# Rev01.net
KiCad netlist of a schematic drawn in EAGLE
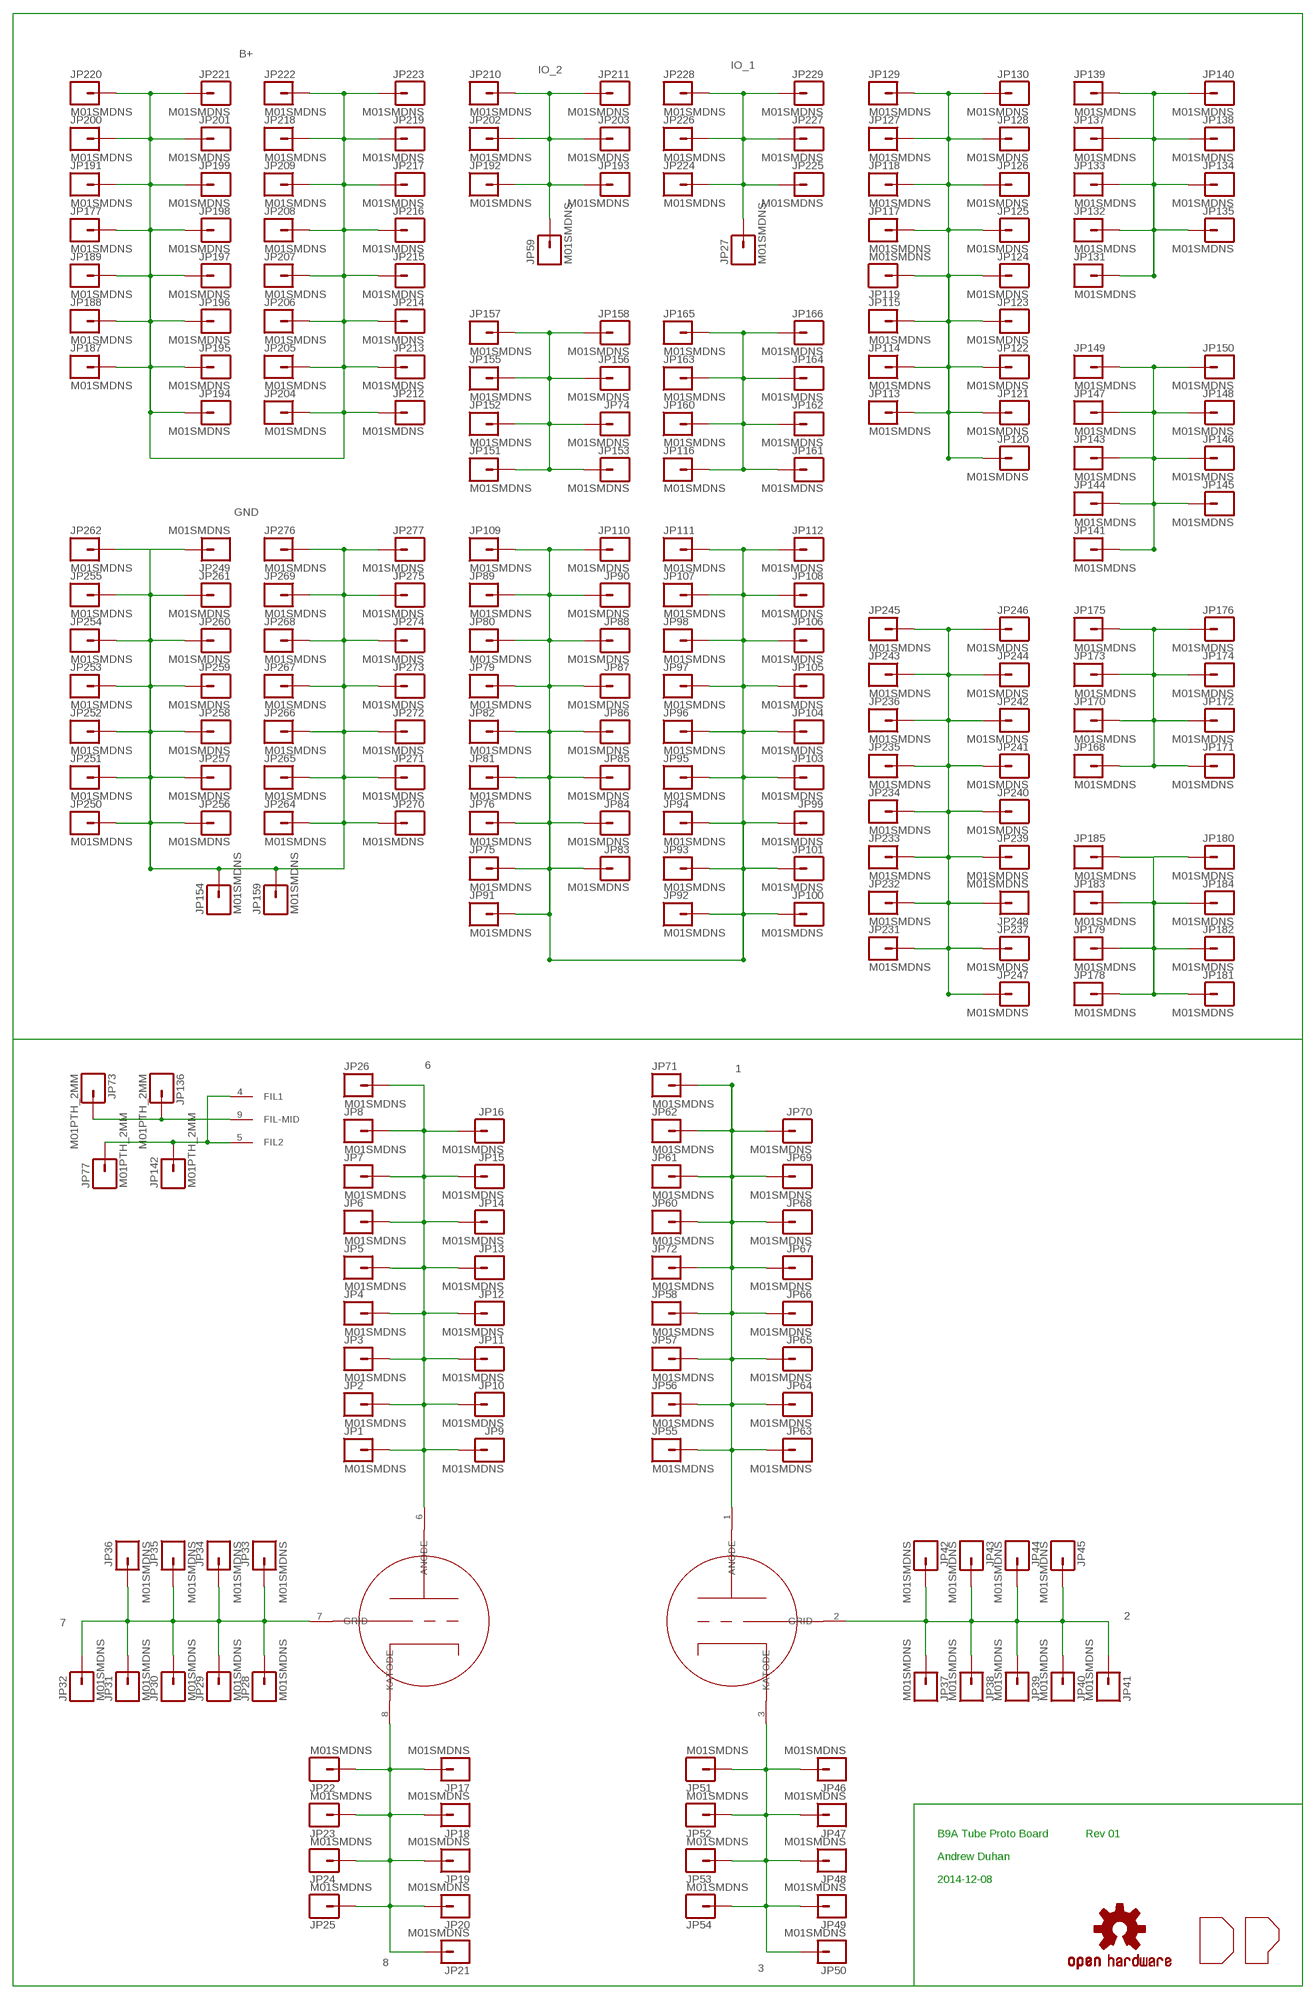
[diagram p0: schematic, sheet 1]

(export (version "E")
  (design (tool "Eeschema 10.0.6"))
  (components
    (comp (ref "JP1")
      (value "M01SMDNS")
      (footprint "eagle-import:1X01NS")
      (libsource (lib "eagle-import") (part "M01SMDNS"))
    )
    (comp (ref "JP2")
      (value "M01SMDNS")
      (footprint "eagle-import:1X01NS")
      (libsource (lib "eagle-import") (part "M01SMDNS"))
    )
    (comp (ref "JP3")
      (value "M01SMDNS")
      (footprint "eagle-import:1X01NS")
      (libsource (lib "eagle-import") (part "M01SMDNS"))
    )
    (comp (ref "JP4")
      (value "M01SMDNS")
      (footprint "eagle-import:1X01NS")
      (libsource (lib "eagle-import") (part "M01SMDNS"))
    )
    (comp (ref "JP5")
      (value "M01SMDNS")
      (footprint "eagle-import:1X01NS")
      (libsource (lib "eagle-import") (part "M01SMDNS"))
    )
    (comp (ref "JP6")
      (value "M01SMDNS")
      (footprint "eagle-import:1X01NS")
      (libsource (lib "eagle-import") (part "M01SMDNS"))
    )
    (comp (ref "JP7")
      (value "M01SMDNS")
      (footprint "eagle-import:1X01NS")
      (libsource (lib "eagle-import") (part "M01SMDNS"))
    )
    (comp (ref "JP8")
      (value "M01SMDNS")
      (footprint "eagle-import:1X01NS")
      (libsource (lib "eagle-import") (part "M01SMDNS"))
    )
    (comp (ref "JP9")
      (value "M01SMDNS")
      (footprint "eagle-import:1X01NS")
      (libsource (lib "eagle-import") (part "M01SMDNS"))
    )
    (comp (ref "JP10")
      (value "M01SMDNS")
      (footprint "eagle-import:1X01NS")
      (libsource (lib "eagle-import") (part "M01SMDNS"))
    )
    (comp (ref "JP11")
      (value "M01SMDNS")
      (footprint "eagle-import:1X01NS")
      (libsource (lib "eagle-import") (part "M01SMDNS"))
    )
    (comp (ref "JP12")
      (value "M01SMDNS")
      (footprint "eagle-import:1X01NS")
      (libsource (lib "eagle-import") (part "M01SMDNS"))
    )
    (comp (ref "JP13")
      (value "M01SMDNS")
      (footprint "eagle-import:1X01NS")
      (libsource (lib "eagle-import") (part "M01SMDNS"))
    )
    (comp (ref "JP14")
      (value "M01SMDNS")
      (footprint "eagle-import:1X01NS")
      (libsource (lib "eagle-import") (part "M01SMDNS"))
    )
    (comp (ref "JP15")
      (value "M01SMDNS")
      (footprint "eagle-import:1X01NS")
      (libsource (lib "eagle-import") (part "M01SMDNS"))
    )
    (comp (ref "JP16")
      (value "M01SMDNS")
      (footprint "eagle-import:1X01NS")
      (libsource (lib "eagle-import") (part "M01SMDNS"))
    )
    (comp (ref "JP17")
      (value "M01SMDNS")
      (footprint "eagle-import:1X01NS")
      (libsource (lib "eagle-import") (part "M01SMDNS"))
    )
    (comp (ref "JP18")
      (value "M01SMDNS")
      (footprint "eagle-import:1X01NS")
      (libsource (lib "eagle-import") (part "M01SMDNS"))
    )
    (comp (ref "JP19")
      (value "M01SMDNS")
      (footprint "eagle-import:1X01NS")
      (libsource (lib "eagle-import") (part "M01SMDNS"))
    )
    (comp (ref "JP20")
      (value "M01SMDNS")
      (footprint "eagle-import:1X01NS")
      (libsource (lib "eagle-import") (part "M01SMDNS"))
    )
    (comp (ref "JP21")
      (value "M01SMDNS")
      (footprint "eagle-import:1X01NS")
      (libsource (lib "eagle-import") (part "M01SMDNS"))
    )
    (comp (ref "JP22")
      (value "M01SMDNS")
      (footprint "eagle-import:1X01NS")
      (libsource (lib "eagle-import") (part "M01SMDNS"))
    )
    (comp (ref "JP23")
      (value "M01SMDNS")
      (footprint "eagle-import:1X01NS")
      (libsource (lib "eagle-import") (part "M01SMDNS"))
    )
    (comp (ref "JP24")
      (value "M01SMDNS")
      (footprint "eagle-import:1X01NS")
      (libsource (lib "eagle-import") (part "M01SMDNS"))
    )
    (comp (ref "JP25")
      (value "M01SMDNS")
      (footprint "eagle-import:1X01NS")
      (libsource (lib "eagle-import") (part "M01SMDNS"))
    )
    (comp (ref "JP26")
      (value "M01SMDNS")
      (footprint "eagle-import:1X01NS")
      (libsource (lib "eagle-import") (part "M01SMDNS"))
    )
    (comp (ref "JP27")
      (value "M01SMDNS")
      (footprint "eagle-import:1X01NS")
      (libsource (lib "eagle-import") (part "M01SMDNS"))
    )
    (comp (ref "JP28")
      (value "M01SMDNS")
      (footprint "eagle-import:1X01NS")
      (libsource (lib "eagle-import") (part "M01SMDNS"))
    )
    (comp (ref "JP29")
      (value "M01SMDNS")
      (footprint "eagle-import:1X01NS")
      (libsource (lib "eagle-import") (part "M01SMDNS"))
    )
    (comp (ref "JP30")
      (value "M01SMDNS")
      (footprint "eagle-import:1X01NS")
      (libsource (lib "eagle-import") (part "M01SMDNS"))
    )
    (comp (ref "JP31")
      (value "M01SMDNS")
      (footprint "eagle-import:1X01NS")
      (libsource (lib "eagle-import") (part "M01SMDNS"))
    )
    (comp (ref "JP32")
      (value "M01SMDNS")
      (footprint "eagle-import:1X01NS")
      (libsource (lib "eagle-import") (part "M01SMDNS"))
    )
    (comp (ref "JP33")
      (value "M01SMDNS")
      (footprint "eagle-import:1X01NS")
      (libsource (lib "eagle-import") (part "M01SMDNS"))
    )
    (comp (ref "JP34")
      (value "M01SMDNS")
      (footprint "eagle-import:1X01NS")
      (libsource (lib "eagle-import") (part "M01SMDNS"))
    )
    (comp (ref "JP35")
      (value "M01SMDNS")
      (footprint "eagle-import:1X01NS")
      (libsource (lib "eagle-import") (part "M01SMDNS"))
    )
    (comp (ref "JP36")
      (value "M01SMDNS")
      (footprint "eagle-import:1X01NS")
      (libsource (lib "eagle-import") (part "M01SMDNS"))
    )
    (comp (ref "JP37")
      (value "M01SMDNS")
      (footprint "eagle-import:1X01NS")
      (libsource (lib "eagle-import") (part "M01SMDNS"))
    )
    (comp (ref "JP38")
      (value "M01SMDNS")
      (footprint "eagle-import:1X01NS")
      (libsource (lib "eagle-import") (part "M01SMDNS"))
    )
    (comp (ref "JP39")
      (value "M01SMDNS")
      (footprint "eagle-import:1X01NS")
      (libsource (lib "eagle-import") (part "M01SMDNS"))
    )
    (comp (ref "JP40")
      (value "M01SMDNS")
      (footprint "eagle-import:1X01NS")
      (libsource (lib "eagle-import") (part "M01SMDNS"))
    )
    (comp (ref "JP41")
      (value "M01SMDNS")
      (footprint "eagle-import:1X01NS")
      (libsource (lib "eagle-import") (part "M01SMDNS"))
    )
    (comp (ref "JP42")
      (value "M01SMDNS")
      (footprint "eagle-import:1X01NS")
      (libsource (lib "eagle-import") (part "M01SMDNS"))
    )
    (comp (ref "JP43")
      (value "M01SMDNS")
      (footprint "eagle-import:1X01NS")
      (libsource (lib "eagle-import") (part "M01SMDNS"))
    )
    (comp (ref "JP44")
      (value "M01SMDNS")
      (footprint "eagle-import:1X01NS")
      (libsource (lib "eagle-import") (part "M01SMDNS"))
    )
    (comp (ref "JP45")
      (value "M01SMDNS")
      (footprint "eagle-import:1X01NS")
      (libsource (lib "eagle-import") (part "M01SMDNS"))
    )
    (comp (ref "JP46")
      (value "M01SMDNS")
      (footprint "eagle-import:1X01NS")
      (libsource (lib "eagle-import") (part "M01SMDNS"))
    )
    (comp (ref "JP47")
      (value "M01SMDNS")
      (footprint "eagle-import:1X01NS")
      (libsource (lib "eagle-import") (part "M01SMDNS"))
    )
    (comp (ref "JP48")
      (value "M01SMDNS")
      (footprint "eagle-import:1X01NS")
      (libsource (lib "eagle-import") (part "M01SMDNS"))
    )
    (comp (ref "JP49")
      (value "M01SMDNS")
      (footprint "eagle-import:1X01NS")
      (libsource (lib "eagle-import") (part "M01SMDNS"))
    )
    (comp (ref "JP50")
      (value "M01SMDNS")
      (footprint "eagle-import:1X01NS")
      (libsource (lib "eagle-import") (part "M01SMDNS"))
    )
    (comp (ref "JP51")
      (value "M01SMDNS")
      (footprint "eagle-import:1X01NS")
      (libsource (lib "eagle-import") (part "M01SMDNS"))
    )
    (comp (ref "JP52")
      (value "M01SMDNS")
      (footprint "eagle-import:1X01NS")
      (libsource (lib "eagle-import") (part "M01SMDNS"))
    )
    (comp (ref "JP53")
      (value "M01SMDNS")
      (footprint "eagle-import:1X01NS")
      (libsource (lib "eagle-import") (part "M01SMDNS"))
    )
    (comp (ref "JP54")
      (value "M01SMDNS")
      (footprint "eagle-import:1X01NS")
      (libsource (lib "eagle-import") (part "M01SMDNS"))
    )
    (comp (ref "JP55")
      (value "M01SMDNS")
      (footprint "eagle-import:1X01NS")
      (libsource (lib "eagle-import") (part "M01SMDNS"))
    )
    (comp (ref "JP56")
      (value "M01SMDNS")
      (footprint "eagle-import:1X01NS")
      (libsource (lib "eagle-import") (part "M01SMDNS"))
    )
    (comp (ref "JP57")
      (value "M01SMDNS")
      (footprint "eagle-import:1X01NS")
      (libsource (lib "eagle-import") (part "M01SMDNS"))
    )
    (comp (ref "JP58")
      (value "M01SMDNS")
      (footprint "eagle-import:1X01NS")
      (libsource (lib "eagle-import") (part "M01SMDNS"))
    )
    (comp (ref "JP59")
      (value "M01SMDNS")
      (footprint "eagle-import:1X01NS")
      (libsource (lib "eagle-import") (part "M01SMDNS"))
    )
    (comp (ref "JP60")
      (value "M01SMDNS")
      (footprint "eagle-import:1X01NS")
      (libsource (lib "eagle-import") (part "M01SMDNS"))
    )
    (comp (ref "JP61")
      (value "M01SMDNS")
      (footprint "eagle-import:1X01NS")
      (libsource (lib "eagle-import") (part "M01SMDNS"))
    )
    (comp (ref "JP62")
      (value "M01SMDNS")
      (footprint "eagle-import:1X01NS")
      (libsource (lib "eagle-import") (part "M01SMDNS"))
    )
    (comp (ref "JP63")
      (value "M01SMDNS")
      (footprint "eagle-import:1X01NS")
      (libsource (lib "eagle-import") (part "M01SMDNS"))
    )
    (comp (ref "JP64")
      (value "M01SMDNS")
      (footprint "eagle-import:1X01NS")
      (libsource (lib "eagle-import") (part "M01SMDNS"))
    )
    (comp (ref "JP65")
      (value "M01SMDNS")
      (footprint "eagle-import:1X01NS")
      (libsource (lib "eagle-import") (part "M01SMDNS"))
    )
    (comp (ref "JP66")
      (value "M01SMDNS")
      (footprint "eagle-import:1X01NS")
      (libsource (lib "eagle-import") (part "M01SMDNS"))
    )
    (comp (ref "JP67")
      (value "M01SMDNS")
      (footprint "eagle-import:1X01NS")
      (libsource (lib "eagle-import") (part "M01SMDNS"))
    )
    (comp (ref "JP68")
      (value "M01SMDNS")
      (footprint "eagle-import:1X01NS")
      (libsource (lib "eagle-import") (part "M01SMDNS"))
    )
    (comp (ref "JP69")
      (value "M01SMDNS")
      (footprint "eagle-import:1X01NS")
      (libsource (lib "eagle-import") (part "M01SMDNS"))
    )
    (comp (ref "JP70")
      (value "M01SMDNS")
      (footprint "eagle-import:1X01NS")
      (libsource (lib "eagle-import") (part "M01SMDNS"))
    )
    (comp (ref "JP71")
      (value "M01SMDNS")
      (footprint "eagle-import:1X01NS")
      (libsource (lib "eagle-import") (part "M01SMDNS"))
    )
    (comp (ref "JP72")
      (value "M01SMDNS")
      (footprint "eagle-import:1X01NS")
      (libsource (lib "eagle-import") (part "M01SMDNS"))
    )
    (comp (ref "JP73")
      (value "M01PTH_2MM")
      (footprint "eagle-import:1X01_2MM")
      (libsource (lib "eagle-import") (part "M01PTH_2MM"))
    )
    (comp (ref "JP74")
      (value "M01SMDNS")
      (footprint "eagle-import:1X01NS")
      (libsource (lib "eagle-import") (part "M01SMDNS"))
    )
    (comp (ref "JP75")
      (value "M01SMDNS")
      (footprint "eagle-import:1X01NS")
      (libsource (lib "eagle-import") (part "M01SMDNS"))
    )
    (comp (ref "JP76")
      (value "M01SMDNS")
      (footprint "eagle-import:1X01NS")
      (libsource (lib "eagle-import") (part "M01SMDNS"))
    )
    (comp (ref "JP77")
      (value "M01PTH_2MM")
      (footprint "eagle-import:1X01_2MM")
      (libsource (lib "eagle-import") (part "M01PTH_2MM"))
    )
    (comp (ref "JP79")
      (value "M01SMDNS")
      (footprint "eagle-import:1X01NS")
      (libsource (lib "eagle-import") (part "M01SMDNS"))
    )
    (comp (ref "JP80")
      (value "M01SMDNS")
      (footprint "eagle-import:1X01NS")
      (libsource (lib "eagle-import") (part "M01SMDNS"))
    )
    (comp (ref "JP81")
      (value "M01SMDNS")
      (footprint "eagle-import:1X01NS")
      (libsource (lib "eagle-import") (part "M01SMDNS"))
    )
    (comp (ref "JP82")
      (value "M01SMDNS")
      (footprint "eagle-import:1X01NS")
      (libsource (lib "eagle-import") (part "M01SMDNS"))
    )
    (comp (ref "JP83")
      (value "M01SMDNS")
      (footprint "eagle-import:1X01NS")
      (libsource (lib "eagle-import") (part "M01SMDNS"))
    )
    (comp (ref "JP84")
      (value "M01SMDNS")
      (footprint "eagle-import:1X01NS")
      (libsource (lib "eagle-import") (part "M01SMDNS"))
    )
    (comp (ref "JP85")
      (value "M01SMDNS")
      (footprint "eagle-import:1X01NS")
      (libsource (lib "eagle-import") (part "M01SMDNS"))
    )
    (comp (ref "JP86")
      (value "M01SMDNS")
      (footprint "eagle-import:1X01NS")
      (libsource (lib "eagle-import") (part "M01SMDNS"))
    )
    (comp (ref "JP87")
      (value "M01SMDNS")
      (footprint "eagle-import:1X01NS")
      (libsource (lib "eagle-import") (part "M01SMDNS"))
    )
    (comp (ref "JP88")
      (value "M01SMDNS")
      (footprint "eagle-import:1X01NS")
      (libsource (lib "eagle-import") (part "M01SMDNS"))
    )
    (comp (ref "JP89")
      (value "M01SMDNS")
      (footprint "eagle-import:1X01NS")
      (libsource (lib "eagle-import") (part "M01SMDNS"))
    )
    (comp (ref "JP90")
      (value "M01SMDNS")
      (footprint "eagle-import:1X01NS")
      (libsource (lib "eagle-import") (part "M01SMDNS"))
    )
    (comp (ref "JP91")
      (value "M01SMDNS")
      (footprint "eagle-import:1X01NS")
      (libsource (lib "eagle-import") (part "M01SMDNS"))
    )
    (comp (ref "JP92")
      (value "M01SMDNS")
      (footprint "eagle-import:1X01NS")
      (libsource (lib "eagle-import") (part "M01SMDNS"))
    )
    (comp (ref "JP93")
      (value "M01SMDNS")
      (footprint "eagle-import:1X01NS")
      (libsource (lib "eagle-import") (part "M01SMDNS"))
    )
    (comp (ref "JP94")
      (value "M01SMDNS")
      (footprint "eagle-import:1X01NS")
      (libsource (lib "eagle-import") (part "M01SMDNS"))
    )
    (comp (ref "JP95")
      (value "M01SMDNS")
      (footprint "eagle-import:1X01NS")
      (libsource (lib "eagle-import") (part "M01SMDNS"))
    )
    (comp (ref "JP96")
      (value "M01SMDNS")
      (footprint "eagle-import:1X01NS")
      (libsource (lib "eagle-import") (part "M01SMDNS"))
    )
    (comp (ref "JP97")
      (value "M01SMDNS")
      (footprint "eagle-import:1X01NS")
      (libsource (lib "eagle-import") (part "M01SMDNS"))
    )
    (comp (ref "JP98")
      (value "M01SMDNS")
      (footprint "eagle-import:1X01NS")
      (libsource (lib "eagle-import") (part "M01SMDNS"))
    )
    (comp (ref "JP99")
      (value "M01SMDNS")
      (footprint "eagle-import:1X01NS")
      (libsource (lib "eagle-import") (part "M01SMDNS"))
    )
    (comp (ref "JP100")
      (value "M01SMDNS")
      (footprint "eagle-import:1X01NS")
      (libsource (lib "eagle-import") (part "M01SMDNS"))
    )
    (comp (ref "JP101")
      (value "M01SMDNS")
      (footprint "eagle-import:1X01NS")
      (libsource (lib "eagle-import") (part "M01SMDNS"))
    )
    (comp (ref "JP103")
      (value "M01SMDNS")
      (footprint "eagle-import:1X01NS")
      (libsource (lib "eagle-import") (part "M01SMDNS"))
    )
    (comp (ref "JP104")
      (value "M01SMDNS")
      (footprint "eagle-import:1X01NS")
      (libsource (lib "eagle-import") (part "M01SMDNS"))
    )
    (comp (ref "JP105")
      (value "M01SMDNS")
      (footprint "eagle-import:1X01NS")
      (libsource (lib "eagle-import") (part "M01SMDNS"))
    )
    (comp (ref "JP106")
      (value "M01SMDNS")
      (footprint "eagle-import:1X01NS")
      (libsource (lib "eagle-import") (part "M01SMDNS"))
    )
    (comp (ref "JP107")
      (value "M01SMDNS")
      (footprint "eagle-import:1X01NS")
      (libsource (lib "eagle-import") (part "M01SMDNS"))
    )
    (comp (ref "JP108")
      (value "M01SMDNS")
      (footprint "eagle-import:1X01NS")
      (libsource (lib "eagle-import") (part "M01SMDNS"))
    )
    (comp (ref "JP109")
      (value "M01SMDNS")
      (footprint "eagle-import:1X01NS")
      (libsource (lib "eagle-import") (part "M01SMDNS"))
    )
    (comp (ref "JP110")
      (value "M01SMDNS")
      (footprint "eagle-import:1X01NS")
      (libsource (lib "eagle-import") (part "M01SMDNS"))
    )
    (comp (ref "JP111")
      (value "M01SMDNS")
      (footprint "eagle-import:1X01NS")
      (libsource (lib "eagle-import") (part "M01SMDNS"))
    )
    (comp (ref "JP112")
      (value "M01SMDNS")
      (footprint "eagle-import:1X01NS")
      (libsource (lib "eagle-import") (part "M01SMDNS"))
    )
    (comp (ref "JP113")
      (value "M01SMDNS")
      (footprint "eagle-import:1X01NS")
      (libsource (lib "eagle-import") (part "M01SMDNS"))
    )
    (comp (ref "JP114")
      (value "M01SMDNS")
      (footprint "eagle-import:1X01NS")
      (libsource (lib "eagle-import") (part "M01SMDNS"))
    )
    (comp (ref "JP115")
      (value "M01SMDNS")
      (footprint "eagle-import:1X01NS")
      (libsource (lib "eagle-import") (part "M01SMDNS"))
    )
    (comp (ref "JP116")
      (value "M01SMDNS")
      (footprint "eagle-import:1X01NS")
      (libsource (lib "eagle-import") (part "M01SMDNS"))
    )
    (comp (ref "JP117")
      (value "M01SMDNS")
      (footprint "eagle-import:1X01NS")
      (libsource (lib "eagle-import") (part "M01SMDNS"))
    )
    (comp (ref "JP118")
      (value "M01SMDNS")
      (footprint "eagle-import:1X01NS")
      (libsource (lib "eagle-import") (part "M01SMDNS"))
    )
    (comp (ref "JP119")
      (value "M01SMDNS")
      (footprint "eagle-import:1X01NS")
      (libsource (lib "eagle-import") (part "M01SMDNS"))
    )
    (comp (ref "JP120")
      (value "M01SMDNS")
      (footprint "eagle-import:1X01NS")
      (libsource (lib "eagle-import") (part "M01SMDNS"))
    )
    (comp (ref "JP121")
      (value "M01SMDNS")
      (footprint "eagle-import:1X01NS")
      (libsource (lib "eagle-import") (part "M01SMDNS"))
    )
    (comp (ref "JP122")
      (value "M01SMDNS")
      (footprint "eagle-import:1X01NS")
      (libsource (lib "eagle-import") (part "M01SMDNS"))
    )
    (comp (ref "JP123")
      (value "M01SMDNS")
      (footprint "eagle-import:1X01NS")
      (libsource (lib "eagle-import") (part "M01SMDNS"))
    )
    (comp (ref "JP124")
      (value "M01SMDNS")
      (footprint "eagle-import:1X01NS")
      (libsource (lib "eagle-import") (part "M01SMDNS"))
    )
    (comp (ref "JP125")
      (value "M01SMDNS")
      (footprint "eagle-import:1X01NS")
      (libsource (lib "eagle-import") (part "M01SMDNS"))
    )
    (comp (ref "JP126")
      (value "M01SMDNS")
      (footprint "eagle-import:1X01NS")
      (libsource (lib "eagle-import") (part "M01SMDNS"))
    )
    (comp (ref "JP127")
      (value "M01SMDNS")
      (footprint "eagle-import:1X01NS")
      (libsource (lib "eagle-import") (part "M01SMDNS"))
    )
    (comp (ref "JP128")
      (value "M01SMDNS")
      (footprint "eagle-import:1X01NS")
      (libsource (lib "eagle-import") (part "M01SMDNS"))
    )
    (comp (ref "JP129")
      (value "M01SMDNS")
      (footprint "eagle-import:1X01NS")
      (libsource (lib "eagle-import") (part "M01SMDNS"))
    )
    (comp (ref "JP130")
      (value "M01SMDNS")
      (footprint "eagle-import:1X01NS")
      (libsource (lib "eagle-import") (part "M01SMDNS"))
    )
    (comp (ref "JP131")
      (value "M01SMDNS")
      (footprint "eagle-import:1X01NS")
      (libsource (lib "eagle-import") (part "M01SMDNS"))
    )
    (comp (ref "JP132")
      (value "M01SMDNS")
      (footprint "eagle-import:1X01NS")
      (libsource (lib "eagle-import") (part "M01SMDNS"))
    )
    (comp (ref "JP133")
      (value "M01SMDNS")
      (footprint "eagle-import:1X01NS")
      (libsource (lib "eagle-import") (part "M01SMDNS"))
    )
    (comp (ref "JP134")
      (value "M01SMDNS")
      (footprint "eagle-import:1X01NS")
      (libsource (lib "eagle-import") (part "M01SMDNS"))
    )
    (comp (ref "JP135")
      (value "M01SMDNS")
      (footprint "eagle-import:1X01NS")
      (libsource (lib "eagle-import") (part "M01SMDNS"))
    )
    (comp (ref "JP136")
      (value "M01PTH_2MM")
      (footprint "eagle-import:1X01_2MM")
      (libsource (lib "eagle-import") (part "M01PTH_2MM"))
    )
    (comp (ref "JP137")
      (value "M01SMDNS")
      (footprint "eagle-import:1X01NS")
      (libsource (lib "eagle-import") (part "M01SMDNS"))
    )
    (comp (ref "JP138")
      (value "M01SMDNS")
      (footprint "eagle-import:1X01NS")
      (libsource (lib "eagle-import") (part "M01SMDNS"))
    )
    (comp (ref "JP139")
      (value "M01SMDNS")
      (footprint "eagle-import:1X01NS")
      (libsource (lib "eagle-import") (part "M01SMDNS"))
    )
    (comp (ref "JP140")
      (value "M01SMDNS")
      (footprint "eagle-import:1X01NS")
      (libsource (lib "eagle-import") (part "M01SMDNS"))
    )
    (comp (ref "JP141")
      (value "M01SMDNS")
      (footprint "eagle-import:1X01NS")
      (libsource (lib "eagle-import") (part "M01SMDNS"))
    )
    (comp (ref "JP142")
      (value "M01PTH_2MM")
      (footprint "eagle-import:1X01_2MM")
      (libsource (lib "eagle-import") (part "M01PTH_2MM"))
    )
    (comp (ref "JP143")
      (value "M01SMDNS")
      (footprint "eagle-import:1X01NS")
      (libsource (lib "eagle-import") (part "M01SMDNS"))
    )
    (comp (ref "JP144")
      (value "M01SMDNS")
      (footprint "eagle-import:1X01NS")
      (libsource (lib "eagle-import") (part "M01SMDNS"))
    )
    (comp (ref "JP145")
      (value "M01SMDNS")
      (footprint "eagle-import:1X01NS")
      (libsource (lib "eagle-import") (part "M01SMDNS"))
    )
    (comp (ref "JP146")
      (value "M01SMDNS")
      (footprint "eagle-import:1X01NS")
      (libsource (lib "eagle-import") (part "M01SMDNS"))
    )
    (comp (ref "JP147")
      (value "M01SMDNS")
      (footprint "eagle-import:1X01NS")
      (libsource (lib "eagle-import") (part "M01SMDNS"))
    )
    (comp (ref "JP148")
      (value "M01SMDNS")
      (footprint "eagle-import:1X01NS")
      (libsource (lib "eagle-import") (part "M01SMDNS"))
    )
    (comp (ref "JP149")
      (value "M01SMDNS")
      (footprint "eagle-import:1X01NS")
      (libsource (lib "eagle-import") (part "M01SMDNS"))
    )
    (comp (ref "JP150")
      (value "M01SMDNS")
      (footprint "eagle-import:1X01NS")
      (libsource (lib "eagle-import") (part "M01SMDNS"))
    )
    (comp (ref "JP151")
      (value "M01SMDNS")
      (footprint "eagle-import:1X01NS")
      (libsource (lib "eagle-import") (part "M01SMDNS"))
    )
    (comp (ref "JP152")
      (value "M01SMDNS")
      (footprint "eagle-import:1X01NS")
      (libsource (lib "eagle-import") (part "M01SMDNS"))
    )
    (comp (ref "JP153")
      (value "M01SMDNS")
      (footprint "eagle-import:1X01NS")
      (libsource (lib "eagle-import") (part "M01SMDNS"))
    )
    (comp (ref "JP154")
      (value "M01SMDNS")
      (footprint "eagle-import:1X01NS")
      (libsource (lib "eagle-import") (part "M01SMDNS"))
    )
    (comp (ref "JP155")
      (value "M01SMDNS")
      (footprint "eagle-import:1X01NS")
      (libsource (lib "eagle-import") (part "M01SMDNS"))
    )
    (comp (ref "JP156")
      (value "M01SMDNS")
      (footprint "eagle-import:1X01NS")
      (libsource (lib "eagle-import") (part "M01SMDNS"))
    )
    (comp (ref "JP157")
      (value "M01SMDNS")
      (footprint "eagle-import:1X01NS")
      (libsource (lib "eagle-import") (part "M01SMDNS"))
    )
    (comp (ref "JP158")
      (value "M01SMDNS")
      (footprint "eagle-import:1X01NS")
      (libsource (lib "eagle-import") (part "M01SMDNS"))
    )
    (comp (ref "JP159")
      (value "M01SMDNS")
      (footprint "eagle-import:1X01NS")
      (libsource (lib "eagle-import") (part "M01SMDNS"))
    )
    (comp (ref "JP160")
      (value "M01SMDNS")
      (footprint "eagle-import:1X01NS")
      (libsource (lib "eagle-import") (part "M01SMDNS"))
    )
    (comp (ref "JP161")
      (value "M01SMDNS")
      (footprint "eagle-import:1X01NS")
      (libsource (lib "eagle-import") (part "M01SMDNS"))
    )
    (comp (ref "JP162")
      (value "M01SMDNS")
      (footprint "eagle-import:1X01NS")
      (libsource (lib "eagle-import") (part "M01SMDNS"))
    )
    (comp (ref "JP163")
      (value "M01SMDNS")
      (footprint "eagle-import:1X01NS")
      (libsource (lib "eagle-import") (part "M01SMDNS"))
    )
    (comp (ref "JP164")
      (value "M01SMDNS")
      (footprint "eagle-import:1X01NS")
      (libsource (lib "eagle-import") (part "M01SMDNS"))
    )
    (comp (ref "JP165")
      (value "M01SMDNS")
      (footprint "eagle-import:1X01NS")
      (libsource (lib "eagle-import") (part "M01SMDNS"))
    )
    (comp (ref "JP166")
      (value "M01SMDNS")
      (footprint "eagle-import:1X01NS")
      (libsource (lib "eagle-import") (part "M01SMDNS"))
    )
    (comp (ref "JP168")
      (value "M01SMDNS")
      (footprint "eagle-import:1X01NS")
      (libsource (lib "eagle-import") (part "M01SMDNS"))
    )
    (comp (ref "JP170")
      (value "M01SMDNS")
      (footprint "eagle-import:1X01NS")
      (libsource (lib "eagle-import") (part "M01SMDNS"))
    )
    (comp (ref "JP171")
      (value "M01SMDNS")
      (footprint "eagle-import:1X01NS")
      (libsource (lib "eagle-import") (part "M01SMDNS"))
    )
    (comp (ref "JP172")
      (value "M01SMDNS")
      (footprint "eagle-import:1X01NS")
      (libsource (lib "eagle-import") (part "M01SMDNS"))
    )
    (comp (ref "JP173")
      (value "M01SMDNS")
      (footprint "eagle-import:1X01NS")
      (libsource (lib "eagle-import") (part "M01SMDNS"))
    )
    (comp (ref "JP174")
      (value "M01SMDNS")
      (footprint "eagle-import:1X01NS")
      (libsource (lib "eagle-import") (part "M01SMDNS"))
    )
    (comp (ref "JP175")
      (value "M01SMDNS")
      (footprint "eagle-import:1X01NS")
      (libsource (lib "eagle-import") (part "M01SMDNS"))
    )
    (comp (ref "JP176")
      (value "M01SMDNS")
      (footprint "eagle-import:1X01NS")
      (libsource (lib "eagle-import") (part "M01SMDNS"))
    )
    (comp (ref "JP177")
      (value "M01SMDNS")
      (footprint "eagle-import:1X01NS")
      (libsource (lib "eagle-import") (part "M01SMDNS"))
    )
    (comp (ref "JP178")
      (value "M01SMDNS")
      (footprint "eagle-import:1X01NS")
      (libsource (lib "eagle-import") (part "M01SMDNS"))
    )
    (comp (ref "JP179")
      (value "M01SMDNS")
      (footprint "eagle-import:1X01NS")
      (libsource (lib "eagle-import") (part "M01SMDNS"))
    )
    (comp (ref "JP180")
      (value "M01SMDNS")
      (footprint "eagle-import:1X01NS")
      (libsource (lib "eagle-import") (part "M01SMDNS"))
    )
    (comp (ref "JP181")
      (value "M01SMDNS")
      (footprint "eagle-import:1X01NS")
      (libsource (lib "eagle-import") (part "M01SMDNS"))
    )
    (comp (ref "JP182")
      (value "M01SMDNS")
      (footprint "eagle-import:1X01NS")
      (libsource (lib "eagle-import") (part "M01SMDNS"))
    )
    (comp (ref "JP183")
      (value "M01SMDNS")
      (footprint "eagle-import:1X01NS")
      (libsource (lib "eagle-import") (part "M01SMDNS"))
    )
    (comp (ref "JP184")
      (value "M01SMDNS")
      (footprint "eagle-import:1X01NS")
      (libsource (lib "eagle-import") (part "M01SMDNS"))
    )
    (comp (ref "JP185")
      (value "M01SMDNS")
      (footprint "eagle-import:1X01NS")
      (libsource (lib "eagle-import") (part "M01SMDNS"))
    )
    (comp (ref "JP187")
      (value "M01SMDNS")
      (footprint "eagle-import:1X01NS")
      (libsource (lib "eagle-import") (part "M01SMDNS"))
    )
    (comp (ref "JP188")
      (value "M01SMDNS")
      (footprint "eagle-import:1X01NS")
      (libsource (lib "eagle-import") (part "M01SMDNS"))
    )
    (comp (ref "JP189")
      (value "M01SMDNS")
      (footprint "eagle-import:1X01NS")
      (libsource (lib "eagle-import") (part "M01SMDNS"))
    )
    (comp (ref "JP191")
      (value "M01SMDNS")
      (footprint "eagle-import:1X01NS")
      (libsource (lib "eagle-import") (part "M01SMDNS"))
    )
    (comp (ref "JP192")
      (value "M01SMDNS")
      (footprint "eagle-import:1X01NS")
      (libsource (lib "eagle-import") (part "M01SMDNS"))
    )
    (comp (ref "JP193")
      (value "M01SMDNS")
      (footprint "eagle-import:1X01NS")
      (libsource (lib "eagle-import") (part "M01SMDNS"))
    )
    (comp (ref "JP194")
      (value "M01SMDNS")
      (footprint "eagle-import:1X01NS")
      (libsource (lib "eagle-import") (part "M01SMDNS"))
    )
    (comp (ref "JP195")
      (value "M01SMDNS")
      (footprint "eagle-import:1X01NS")
      (libsource (lib "eagle-import") (part "M01SMDNS"))
    )
    (comp (ref "JP196")
      (value "M01SMDNS")
      (footprint "eagle-import:1X01NS")
      (libsource (lib "eagle-import") (part "M01SMDNS"))
    )
    (comp (ref "JP197")
      (value "M01SMDNS")
      (footprint "eagle-import:1X01NS")
      (libsource (lib "eagle-import") (part "M01SMDNS"))
    )
    (comp (ref "JP198")
      (value "M01SMDNS")
      (footprint "eagle-import:1X01NS")
      (libsource (lib "eagle-import") (part "M01SMDNS"))
    )
    (comp (ref "JP199")
      (value "M01SMDNS")
      (footprint "eagle-import:1X01NS")
      (libsource (lib "eagle-import") (part "M01SMDNS"))
    )
    (comp (ref "JP200")
      (value "M01SMDNS")
      (footprint "eagle-import:1X01NS")
      (libsource (lib "eagle-import") (part "M01SMDNS"))
    )
    (comp (ref "JP201")
      (value "M01SMDNS")
      (footprint "eagle-import:1X01NS")
      (libsource (lib "eagle-import") (part "M01SMDNS"))
    )
    (comp (ref "JP202")
      (value "M01SMDNS")
      (footprint "eagle-import:1X01NS")
      (libsource (lib "eagle-import") (part "M01SMDNS"))
    )
    (comp (ref "JP203")
      (value "M01SMDNS")
      (footprint "eagle-import:1X01NS")
      (libsource (lib "eagle-import") (part "M01SMDNS"))
    )
    (comp (ref "JP204")
      (value "M01SMDNS")
      (footprint "eagle-import:1X01NS")
      (libsource (lib "eagle-import") (part "M01SMDNS"))
    )
    (comp (ref "JP205")
      (value "M01SMDNS")
      (footprint "eagle-import:1X01NS")
      (libsource (lib "eagle-import") (part "M01SMDNS"))
    )
    (comp (ref "JP206")
      (value "M01SMDNS")
      (footprint "eagle-import:1X01NS")
      (libsource (lib "eagle-import") (part "M01SMDNS"))
    )
    (comp (ref "JP207")
      (value "M01SMDNS")
      (footprint "eagle-import:1X01NS")
      (libsource (lib "eagle-import") (part "M01SMDNS"))
    )
    (comp (ref "JP208")
      (value "M01SMDNS")
      (footprint "eagle-import:1X01NS")
      (libsource (lib "eagle-import") (part "M01SMDNS"))
    )
    (comp (ref "JP209")
      (value "M01SMDNS")
      (footprint "eagle-import:1X01NS")
      (libsource (lib "eagle-import") (part "M01SMDNS"))
    )
    (comp (ref "JP210")
      (value "M01SMDNS")
      (footprint "eagle-import:1X01NS")
      (libsource (lib "eagle-import") (part "M01SMDNS"))
    )
    (comp (ref "JP211")
      (value "M01SMDNS")
      (footprint "eagle-import:1X01NS")
      (libsource (lib "eagle-import") (part "M01SMDNS"))
    )
    (comp (ref "JP212")
      (value "M01SMDNS")
      (footprint "eagle-import:1X01NS")
      (libsource (lib "eagle-import") (part "M01SMDNS"))
    )
    (comp (ref "JP213")
      (value "M01SMDNS")
      (footprint "eagle-import:1X01NS")
      (libsource (lib "eagle-import") (part "M01SMDNS"))
    )
    (comp (ref "JP214")
      (value "M01SMDNS")
      (footprint "eagle-import:1X01NS")
      (libsource (lib "eagle-import") (part "M01SMDNS"))
    )
    (comp (ref "JP215")
      (value "M01SMDNS")
      (footprint "eagle-import:1X01NS")
      (libsource (lib "eagle-import") (part "M01SMDNS"))
    )
    (comp (ref "JP216")
      (value "M01SMDNS")
      (footprint "eagle-import:1X01NS")
      (libsource (lib "eagle-import") (part "M01SMDNS"))
    )
    (comp (ref "JP217")
      (value "M01SMDNS")
      (footprint "eagle-import:1X01NS")
      (libsource (lib "eagle-import") (part "M01SMDNS"))
    )
    (comp (ref "JP218")
      (value "M01SMDNS")
      (footprint "eagle-import:1X01NS")
      (libsource (lib "eagle-import") (part "M01SMDNS"))
    )
    (comp (ref "JP219")
      (value "M01SMDNS")
      (footprint "eagle-import:1X01NS")
      (libsource (lib "eagle-import") (part "M01SMDNS"))
    )
    (comp (ref "JP220")
      (value "M01SMDNS")
      (footprint "eagle-import:1X01NS")
      (libsource (lib "eagle-import") (part "M01SMDNS"))
    )
    (comp (ref "JP221")
      (value "M01SMDNS")
      (footprint "eagle-import:1X01NS")
      (libsource (lib "eagle-import") (part "M01SMDNS"))
    )
    (comp (ref "JP222")
      (value "M01SMDNS")
      (footprint "eagle-import:1X01NS")
      (libsource (lib "eagle-import") (part "M01SMDNS"))
    )
    (comp (ref "JP223")
      (value "M01SMDNS")
      (footprint "eagle-import:1X01NS")
      (libsource (lib "eagle-import") (part "M01SMDNS"))
    )
    (comp (ref "JP224")
      (value "M01SMDNS")
      (footprint "eagle-import:1X01NS")
      (libsource (lib "eagle-import") (part "M01SMDNS"))
    )
    (comp (ref "JP225")
      (value "M01SMDNS")
      (footprint "eagle-import:1X01NS")
      (libsource (lib "eagle-import") (part "M01SMDNS"))
    )
    (comp (ref "JP226")
      (value "M01SMDNS")
      (footprint "eagle-import:1X01NS")
      (libsource (lib "eagle-import") (part "M01SMDNS"))
    )
    (comp (ref "JP227")
      (value "M01SMDNS")
      (footprint "eagle-import:1X01NS")
      (libsource (lib "eagle-import") (part "M01SMDNS"))
    )
    (comp (ref "JP228")
      (value "M01SMDNS")
      (footprint "eagle-import:1X01NS")
      (libsource (lib "eagle-import") (part "M01SMDNS"))
    )
    (comp (ref "JP229")
      (value "M01SMDNS")
      (footprint "eagle-import:1X01NS")
      (libsource (lib "eagle-import") (part "M01SMDNS"))
    )
    (comp (ref "JP231")
      (value "M01SMDNS")
      (footprint "eagle-import:1X01NS")
      (libsource (lib "eagle-import") (part "M01SMDNS"))
    )
    (comp (ref "JP232")
      (value "M01SMDNS")
      (footprint "eagle-import:1X01NS")
      (libsource (lib "eagle-import") (part "M01SMDNS"))
    )
    (comp (ref "JP233")
      (value "M01SMDNS")
      (footprint "eagle-import:1X01NS")
      (libsource (lib "eagle-import") (part "M01SMDNS"))
    )
    (comp (ref "JP234")
      (value "M01SMDNS")
      (footprint "eagle-import:1X01NS")
      (libsource (lib "eagle-import") (part "M01SMDNS"))
    )
    (comp (ref "JP235")
      (value "M01SMDNS")
      (footprint "eagle-import:1X01NS")
      (libsource (lib "eagle-import") (part "M01SMDNS"))
    )
    (comp (ref "JP236")
      (value "M01SMDNS")
      (footprint "eagle-import:1X01NS")
      (libsource (lib "eagle-import") (part "M01SMDNS"))
    )
    (comp (ref "JP237")
      (value "M01SMDNS")
      (footprint "eagle-import:1X01NS")
      (libsource (lib "eagle-import") (part "M01SMDNS"))
    )
    (comp (ref "JP239")
      (value "M01SMDNS")
      (footprint "eagle-import:1X01NS")
      (libsource (lib "eagle-import") (part "M01SMDNS"))
    )
    (comp (ref "JP240")
      (value "M01SMDNS")
      (footprint "eagle-import:1X01NS")
      (libsource (lib "eagle-import") (part "M01SMDNS"))
    )
    (comp (ref "JP241")
      (value "M01SMDNS")
      (footprint "eagle-import:1X01NS")
      (libsource (lib "eagle-import") (part "M01SMDNS"))
    )
    (comp (ref "JP242")
      (value "M01SMDNS")
      (footprint "eagle-import:1X01NS")
      (libsource (lib "eagle-import") (part "M01SMDNS"))
    )
    (comp (ref "JP243")
      (value "M01SMDNS")
      (footprint "eagle-import:1X01NS")
      (libsource (lib "eagle-import") (part "M01SMDNS"))
    )
    (comp (ref "JP244")
      (value "M01SMDNS")
      (footprint "eagle-import:1X01NS")
      (libsource (lib "eagle-import") (part "M01SMDNS"))
    )
    (comp (ref "JP245")
      (value "M01SMDNS")
      (footprint "eagle-import:1X01NS")
      (libsource (lib "eagle-import") (part "M01SMDNS"))
    )
    (comp (ref "JP246")
      (value "M01SMDNS")
      (footprint "eagle-import:1X01NS")
      (libsource (lib "eagle-import") (part "M01SMDNS"))
    )
    (comp (ref "JP247")
      (value "M01SMDNS")
      (footprint "eagle-import:1X01NS")
      (libsource (lib "eagle-import") (part "M01SMDNS"))
    )
    (comp (ref "JP248")
      (value "M01SMDNS")
      (footprint "eagle-import:1X01NS")
      (libsource (lib "eagle-import") (part "M01SMDNS"))
    )
    (comp (ref "JP249")
      (value "M01SMDNS")
      (footprint "eagle-import:1X01NS")
      (libsource (lib "eagle-import") (part "M01SMDNS"))
    )
    (comp (ref "JP250")
      (value "M01SMDNS")
      (footprint "eagle-import:1X01NS")
      (libsource (lib "eagle-import") (part "M01SMDNS"))
    )
    (comp (ref "JP251")
      (value "M01SMDNS")
      (footprint "eagle-import:1X01NS")
      (libsource (lib "eagle-import") (part "M01SMDNS"))
    )
    (comp (ref "JP252")
      (value "M01SMDNS")
      (footprint "eagle-import:1X01NS")
      (libsource (lib "eagle-import") (part "M01SMDNS"))
    )
    (comp (ref "JP253")
      (value "M01SMDNS")
      (footprint "eagle-import:1X01NS")
      (libsource (lib "eagle-import") (part "M01SMDNS"))
    )
    (comp (ref "JP254")
      (value "M01SMDNS")
      (footprint "eagle-import:1X01NS")
      (libsource (lib "eagle-import") (part "M01SMDNS"))
    )
    (comp (ref "JP255")
      (value "M01SMDNS")
      (footprint "eagle-import:1X01NS")
      (libsource (lib "eagle-import") (part "M01SMDNS"))
    )
    (comp (ref "JP256")
      (value "M01SMDNS")
      (footprint "eagle-import:1X01NS")
      (libsource (lib "eagle-import") (part "M01SMDNS"))
    )
    (comp (ref "JP257")
      (value "M01SMDNS")
      (footprint "eagle-import:1X01NS")
      (libsource (lib "eagle-import") (part "M01SMDNS"))
    )
    (comp (ref "JP258")
      (value "M01SMDNS")
      (footprint "eagle-import:1X01NS")
      (libsource (lib "eagle-import") (part "M01SMDNS"))
    )
    (comp (ref "JP259")
      (value "M01SMDNS")
      (footprint "eagle-import:1X01NS")
      (libsource (lib "eagle-import") (part "M01SMDNS"))
    )
    (comp (ref "JP260")
      (value "M01SMDNS")
      (footprint "eagle-import:1X01NS")
      (libsource (lib "eagle-import") (part "M01SMDNS"))
    )
    (comp (ref "JP261")
      (value "M01SMDNS")
      (footprint "eagle-import:1X01NS")
      (libsource (lib "eagle-import") (part "M01SMDNS"))
    )
    (comp (ref "JP262")
      (value "M01SMDNS")
      (footprint "eagle-import:1X01NS")
      (libsource (lib "eagle-import") (part "M01SMDNS"))
    )
    (comp (ref "JP264")
      (value "M01SMDNS")
      (footprint "eagle-import:1X01NS")
      (libsource (lib "eagle-import") (part "M01SMDNS"))
    )
    (comp (ref "JP265")
      (value "M01SMDNS")
      (footprint "eagle-import:1X01NS")
      (libsource (lib "eagle-import") (part "M01SMDNS"))
    )
    (comp (ref "JP266")
      (value "M01SMDNS")
      (footprint "eagle-import:1X01NS")
      (libsource (lib "eagle-import") (part "M01SMDNS"))
    )
    (comp (ref "JP267")
      (value "M01SMDNS")
      (footprint "eagle-import:1X01NS")
      (libsource (lib "eagle-import") (part "M01SMDNS"))
    )
    (comp (ref "JP268")
      (value "M01SMDNS")
      (footprint "eagle-import:1X01NS")
      (libsource (lib "eagle-import") (part "M01SMDNS"))
    )
    (comp (ref "JP269")
      (value "M01SMDNS")
      (footprint "eagle-import:1X01NS")
      (libsource (lib "eagle-import") (part "M01SMDNS"))
    )
    (comp (ref "JP270")
      (value "M01SMDNS")
      (footprint "eagle-import:1X01NS")
      (libsource (lib "eagle-import") (part "M01SMDNS"))
    )
    (comp (ref "JP271")
      (value "M01SMDNS")
      (footprint "eagle-import:1X01NS")
      (libsource (lib "eagle-import") (part "M01SMDNS"))
    )
    (comp (ref "JP272")
      (value "M01SMDNS")
      (footprint "eagle-import:1X01NS")
      (libsource (lib "eagle-import") (part "M01SMDNS"))
    )
    (comp (ref "JP273")
      (value "M01SMDNS")
      (footprint "eagle-import:1X01NS")
      (libsource (lib "eagle-import") (part "M01SMDNS"))
    )
    (comp (ref "JP274")
      (value "M01SMDNS")
      (footprint "eagle-import:1X01NS")
      (libsource (lib "eagle-import") (part "M01SMDNS"))
    )
    (comp (ref "JP275")
      (value "M01SMDNS")
      (footprint "eagle-import:1X01NS")
      (libsource (lib "eagle-import") (part "M01SMDNS"))
    )
    (comp (ref "JP276")
      (value "M01SMDNS")
      (footprint "eagle-import:1X01NS")
      (libsource (lib "eagle-import") (part "M01SMDNS"))
    )
    (comp (ref "JP277")
      (value "M01SMDNS")
      (footprint "eagle-import:1X01NS")
      (libsource (lib "eagle-import") (part "M01SMDNS"))
    )
    (comp (ref "LOGO1")
      (value "OSHW-LOGOM")
      (footprint "eagle-import:OSHW-LOGO-M")
      (libsource (lib "eagle-import") (part "OSHW-LOGOM"))
    )
    (comp (ref "U$1")
      (value "12AX7")
      (footprint "eagle-import:12AX7-ROUND")
      (libsource (lib "eagle-import") (part "12AX7"))
    )
    (comp (ref "U$2")
      (value "DP_LOGO")
      (footprint "eagle-import:DP_LOGO")
      (libsource (lib "eagle-import") (part "DP_LOGO"))
    )
  )
  (nets
    (net (code "1") (name "/1") (class "Default")
      (node (ref "JP55") (pin "1") (pinfunction "1_1") (pintype "passive"))
      (node (ref "JP56") (pin "1") (pinfunction "1_1") (pintype "passive"))
      (node (ref "JP57") (pin "1") (pinfunction "1_1") (pintype "passive"))
      (node (ref "JP58") (pin "1") (pinfunction "1_1") (pintype "passive"))
      (node (ref "JP60") (pin "1") (pinfunction "1_1") (pintype "passive"))
      (node (ref "JP61") (pin "1") (pinfunction "1_1") (pintype "passive"))
      (node (ref "JP62") (pin "1") (pinfunction "1_1") (pintype "passive"))
      (node (ref "JP63") (pin "1") (pinfunction "1_1") (pintype "passive"))
      (node (ref "JP64") (pin "1") (pinfunction "1_1") (pintype "passive"))
      (node (ref "JP65") (pin "1") (pinfunction "1_1") (pintype "passive"))
      (node (ref "JP66") (pin "1") (pinfunction "1_1") (pintype "passive"))
      (node (ref "JP67") (pin "1") (pinfunction "1_1") (pintype "passive"))
      (node (ref "JP68") (pin "1") (pinfunction "1_1") (pintype "passive"))
      (node (ref "JP69") (pin "1") (pinfunction "1_1") (pintype "passive"))
      (node (ref "JP70") (pin "1") (pinfunction "1_1") (pintype "passive"))
      (node (ref "JP71") (pin "1") (pinfunction "1_1") (pintype "passive"))
      (node (ref "JP72") (pin "1") (pinfunction "1_1") (pintype "passive"))
      (node (ref "U$1") (pin "1") (pinfunction "ANODE_1") (pintype "bidirectional"))
    )
    (net (code "2") (name "/2") (class "Default")
      (node (ref "JP37") (pin "1") (pinfunction "1_1") (pintype "passive"))
      (node (ref "JP38") (pin "1") (pinfunction "1_1") (pintype "passive"))
      (node (ref "JP39") (pin "1") (pinfunction "1_1") (pintype "passive"))
      (node (ref "JP40") (pin "1") (pinfunction "1_1") (pintype "passive"))
      (node (ref "JP41") (pin "1") (pinfunction "1_1") (pintype "passive"))
      (node (ref "JP42") (pin "1") (pinfunction "1_1") (pintype "passive"))
      (node (ref "JP43") (pin "1") (pinfunction "1_1") (pintype "passive"))
      (node (ref "JP44") (pin "1") (pinfunction "1_1") (pintype "passive"))
      (node (ref "JP45") (pin "1") (pinfunction "1_1") (pintype "passive"))
      (node (ref "U$1") (pin "2") (pinfunction "GRID_2") (pintype "bidirectional"))
    )
    (net (code "3") (name "/3") (class "Default")
      (node (ref "JP46") (pin "1") (pinfunction "1_1") (pintype "passive"))
      (node (ref "JP47") (pin "1") (pinfunction "1_1") (pintype "passive"))
      (node (ref "JP48") (pin "1") (pinfunction "1_1") (pintype "passive"))
      (node (ref "JP49") (pin "1") (pinfunction "1_1") (pintype "passive"))
      (node (ref "JP50") (pin "1") (pinfunction "1_1") (pintype "passive"))
      (node (ref "JP51") (pin "1") (pinfunction "1_1") (pintype "passive"))
      (node (ref "JP52") (pin "1") (pinfunction "1_1") (pintype "passive"))
      (node (ref "JP53") (pin "1") (pinfunction "1_1") (pintype "passive"))
      (node (ref "JP54") (pin "1") (pinfunction "1_1") (pintype "passive"))
      (node (ref "U$1") (pin "3") (pinfunction "KATODE_3") (pintype "bidirectional"))
    )
    (net (code "4") (name "/6") (class "Default")
      (node (ref "JP1") (pin "1") (pinfunction "1_1") (pintype "passive"))
      (node (ref "JP10") (pin "1") (pinfunction "1_1") (pintype "passive"))
      (node (ref "JP11") (pin "1") (pinfunction "1_1") (pintype "passive"))
      (node (ref "JP12") (pin "1") (pinfunction "1_1") (pintype "passive"))
      (node (ref "JP13") (pin "1") (pinfunction "1_1") (pintype "passive"))
      (node (ref "JP14") (pin "1") (pinfunction "1_1") (pintype "passive"))
      (node (ref "JP15") (pin "1") (pinfunction "1_1") (pintype "passive"))
      (node (ref "JP16") (pin "1") (pinfunction "1_1") (pintype "passive"))
      (node (ref "JP2") (pin "1") (pinfunction "1_1") (pintype "passive"))
      (node (ref "JP26") (pin "1") (pinfunction "1_1") (pintype "passive"))
      (node (ref "JP3") (pin "1") (pinfunction "1_1") (pintype "passive"))
      (node (ref "JP4") (pin "1") (pinfunction "1_1") (pintype "passive"))
      (node (ref "JP5") (pin "1") (pinfunction "1_1") (pintype "passive"))
      (node (ref "JP6") (pin "1") (pinfunction "1_1") (pintype "passive"))
      (node (ref "JP7") (pin "1") (pinfunction "1_1") (pintype "passive"))
      (node (ref "JP8") (pin "1") (pinfunction "1_1") (pintype "passive"))
      (node (ref "JP9") (pin "1") (pinfunction "1_1") (pintype "passive"))
      (node (ref "U$1") (pin "6") (pinfunction "ANODE_6") (pintype "bidirectional"))
    )
    (net (code "5") (name "/7") (class "Default")
      (node (ref "JP28") (pin "1") (pinfunction "1_1") (pintype "passive"))
      (node (ref "JP29") (pin "1") (pinfunction "1_1") (pintype "passive"))
      (node (ref "JP30") (pin "1") (pinfunction "1_1") (pintype "passive"))
      (node (ref "JP31") (pin "1") (pinfunction "1_1") (pintype "passive"))
      (node (ref "JP32") (pin "1") (pinfunction "1_1") (pintype "passive"))
      (node (ref "JP33") (pin "1") (pinfunction "1_1") (pintype "passive"))
      (node (ref "JP34") (pin "1") (pinfunction "1_1") (pintype "passive"))
      (node (ref "JP35") (pin "1") (pinfunction "1_1") (pintype "passive"))
      (node (ref "JP36") (pin "1") (pinfunction "1_1") (pintype "passive"))
      (node (ref "U$1") (pin "7") (pinfunction "GRID_7") (pintype "bidirectional"))
    )
    (net (code "6") (name "/8") (class "Default")
      (node (ref "JP17") (pin "1") (pinfunction "1_1") (pintype "passive"))
      (node (ref "JP18") (pin "1") (pinfunction "1_1") (pintype "passive"))
      (node (ref "JP19") (pin "1") (pinfunction "1_1") (pintype "passive"))
      (node (ref "JP20") (pin "1") (pinfunction "1_1") (pintype "passive"))
      (node (ref "JP21") (pin "1") (pinfunction "1_1") (pintype "passive"))
      (node (ref "JP22") (pin "1") (pinfunction "1_1") (pintype "passive"))
      (node (ref "JP23") (pin "1") (pinfunction "1_1") (pintype "passive"))
      (node (ref "JP24") (pin "1") (pinfunction "1_1") (pintype "passive"))
      (node (ref "JP25") (pin "1") (pinfunction "1_1") (pintype "passive"))
      (node (ref "U$1") (pin "8") (pinfunction "KATODE_8") (pintype "bidirectional"))
    )
    (net (code "7") (name "/B+") (class "Default")
      (node (ref "JP177") (pin "1") (pinfunction "1_1") (pintype "passive"))
      (node (ref "JP187") (pin "1") (pinfunction "1_1") (pintype "passive"))
      (node (ref "JP188") (pin "1") (pinfunction "1_1") (pintype "passive"))
      (node (ref "JP189") (pin "1") (pinfunction "1_1") (pintype "passive"))
      (node (ref "JP191") (pin "1") (pinfunction "1_1") (pintype "passive"))
      (node (ref "JP194") (pin "1") (pinfunction "1_1") (pintype "passive"))
      (node (ref "JP195") (pin "1") (pinfunction "1_1") (pintype "passive"))
      (node (ref "JP196") (pin "1") (pinfunction "1_1") (pintype "passive"))
      (node (ref "JP197") (pin "1") (pinfunction "1_1") (pintype "passive"))
      (node (ref "JP198") (pin "1") (pinfunction "1_1") (pintype "passive"))
      (node (ref "JP199") (pin "1") (pinfunction "1_1") (pintype "passive"))
      (node (ref "JP200") (pin "1") (pinfunction "1_1") (pintype "passive"))
      (node (ref "JP201") (pin "1") (pinfunction "1_1") (pintype "passive"))
      (node (ref "JP204") (pin "1") (pinfunction "1_1") (pintype "passive"))
      (node (ref "JP205") (pin "1") (pinfunction "1_1") (pintype "passive"))
      (node (ref "JP206") (pin "1") (pinfunction "1_1") (pintype "passive"))
      (node (ref "JP207") (pin "1") (pinfunction "1_1") (pintype "passive"))
      (node (ref "JP208") (pin "1") (pinfunction "1_1") (pintype "passive"))
      (node (ref "JP209") (pin "1") (pinfunction "1_1") (pintype "passive"))
      (node (ref "JP212") (pin "1") (pinfunction "1_1") (pintype "passive"))
      (node (ref "JP213") (pin "1") (pinfunction "1_1") (pintype "passive"))
      (node (ref "JP214") (pin "1") (pinfunction "1_1") (pintype "passive"))
      (node (ref "JP215") (pin "1") (pinfunction "1_1") (pintype "passive"))
      (node (ref "JP216") (pin "1") (pinfunction "1_1") (pintype "passive"))
      (node (ref "JP217") (pin "1") (pinfunction "1_1") (pintype "passive"))
      (node (ref "JP218") (pin "1") (pinfunction "1_1") (pintype "passive"))
      (node (ref "JP219") (pin "1") (pinfunction "1_1") (pintype "passive"))
      (node (ref "JP220") (pin "1") (pinfunction "1_1") (pintype "passive"))
      (node (ref "JP221") (pin "1") (pinfunction "1_1") (pintype "passive"))
      (node (ref "JP222") (pin "1") (pinfunction "1_1") (pintype "passive"))
      (node (ref "JP223") (pin "1") (pinfunction "1_1") (pintype "passive"))
    )
    (net (code "8") (name "/GND") (class "Default")
      (node (ref "JP154") (pin "1") (pinfunction "1_1") (pintype "passive"))
      (node (ref "JP159") (pin "1") (pinfunction "1_1") (pintype "passive"))
      (node (ref "JP249") (pin "1") (pinfunction "1_1") (pintype "passive"))
      (node (ref "JP250") (pin "1") (pinfunction "1_1") (pintype "passive"))
      (node (ref "JP251") (pin "1") (pinfunction "1_1") (pintype "passive"))
      (node (ref "JP252") (pin "1") (pinfunction "1_1") (pintype "passive"))
      (node (ref "JP253") (pin "1") (pinfunction "1_1") (pintype "passive"))
      (node (ref "JP254") (pin "1") (pinfunction "1_1") (pintype "passive"))
      (node (ref "JP255") (pin "1") (pinfunction "1_1") (pintype "passive"))
      (node (ref "JP256") (pin "1") (pinfunction "1_1") (pintype "passive"))
      (node (ref "JP257") (pin "1") (pinfunction "1_1") (pintype "passive"))
      (node (ref "JP258") (pin "1") (pinfunction "1_1") (pintype "passive"))
      (node (ref "JP259") (pin "1") (pinfunction "1_1") (pintype "passive"))
      (node (ref "JP260") (pin "1") (pinfunction "1_1") (pintype "passive"))
      (node (ref "JP261") (pin "1") (pinfunction "1_1") (pintype "passive"))
      (node (ref "JP262") (pin "1") (pinfunction "1_1") (pintype "passive"))
      (node (ref "JP264") (pin "1") (pinfunction "1_1") (pintype "passive"))
      (node (ref "JP265") (pin "1") (pinfunction "1_1") (pintype "passive"))
      (node (ref "JP266") (pin "1") (pinfunction "1_1") (pintype "passive"))
      (node (ref "JP267") (pin "1") (pinfunction "1_1") (pintype "passive"))
      (node (ref "JP268") (pin "1") (pinfunction "1_1") (pintype "passive"))
      (node (ref "JP269") (pin "1") (pinfunction "1_1") (pintype "passive"))
      (node (ref "JP270") (pin "1") (pinfunction "1_1") (pintype "passive"))
      (node (ref "JP271") (pin "1") (pinfunction "1_1") (pintype "passive"))
      (node (ref "JP272") (pin "1") (pinfunction "1_1") (pintype "passive"))
      (node (ref "JP273") (pin "1") (pinfunction "1_1") (pintype "passive"))
      (node (ref "JP274") (pin "1") (pinfunction "1_1") (pintype "passive"))
      (node (ref "JP275") (pin "1") (pinfunction "1_1") (pintype "passive"))
      (node (ref "JP276") (pin "1") (pinfunction "1_1") (pintype "passive"))
      (node (ref "JP277") (pin "1") (pinfunction "1_1") (pintype "passive"))
    )
    (net (code "9") (name "/IO_1") (class "Default")
      (node (ref "JP224") (pin "1") (pinfunction "1_1") (pintype "passive"))
      (node (ref "JP225") (pin "1") (pinfunction "1_1") (pintype "passive"))
      (node (ref "JP226") (pin "1") (pinfunction "1_1") (pintype "passive"))
      (node (ref "JP227") (pin "1") (pinfunction "1_1") (pintype "passive"))
      (node (ref "JP228") (pin "1") (pinfunction "1_1") (pintype "passive"))
      (node (ref "JP229") (pin "1") (pinfunction "1_1") (pintype "passive"))
      (node (ref "JP27") (pin "1") (pinfunction "1_1") (pintype "passive"))
    )
    (net (code "10") (name "/IO_2") (class "Default")
      (node (ref "JP192") (pin "1") (pinfunction "1_1") (pintype "passive"))
      (node (ref "JP193") (pin "1") (pinfunction "1_1") (pintype "passive"))
      (node (ref "JP202") (pin "1") (pinfunction "1_1") (pintype "passive"))
      (node (ref "JP203") (pin "1") (pinfunction "1_1") (pintype "passive"))
      (node (ref "JP210") (pin "1") (pinfunction "1_1") (pintype "passive"))
      (node (ref "JP211") (pin "1") (pinfunction "1_1") (pintype "passive"))
      (node (ref "JP59") (pin "1") (pinfunction "1_1") (pintype "passive"))
    )
    (net (code "11") (name "Net-(JP100-Pad1)") (class "Default")
      (node (ref "JP100") (pin "1") (pinfunction "1_1") (pintype "passive"))
      (node (ref "JP101") (pin "1") (pinfunction "1_1") (pintype "passive"))
      (node (ref "JP103") (pin "1") (pinfunction "1_1") (pintype "passive"))
      (node (ref "JP104") (pin "1") (pinfunction "1_1") (pintype "passive"))
      (node (ref "JP105") (pin "1") (pinfunction "1_1") (pintype "passive"))
      (node (ref "JP106") (pin "1") (pinfunction "1_1") (pintype "passive"))
      (node (ref "JP107") (pin "1") (pinfunction "1_1") (pintype "passive"))
      (node (ref "JP108") (pin "1") (pinfunction "1_1") (pintype "passive"))
      (node (ref "JP109") (pin "1") (pinfunction "1_1") (pintype "passive"))
      (node (ref "JP110") (pin "1") (pinfunction "1_1") (pintype "passive"))
      (node (ref "JP111") (pin "1") (pinfunction "1_1") (pintype "passive"))
      (node (ref "JP112") (pin "1") (pinfunction "1_1") (pintype "passive"))
      (node (ref "JP75") (pin "1") (pinfunction "1_1") (pintype "passive"))
      (node (ref "JP76") (pin "1") (pinfunction "1_1") (pintype "passive"))
      (node (ref "JP79") (pin "1") (pinfunction "1_1") (pintype "passive"))
      (node (ref "JP80") (pin "1") (pinfunction "1_1") (pintype "passive"))
      (node (ref "JP81") (pin "1") (pinfunction "1_1") (pintype "passive"))
      (node (ref "JP82") (pin "1") (pinfunction "1_1") (pintype "passive"))
      (node (ref "JP83") (pin "1") (pinfunction "1_1") (pintype "passive"))
      (node (ref "JP84") (pin "1") (pinfunction "1_1") (pintype "passive"))
      (node (ref "JP85") (pin "1") (pinfunction "1_1") (pintype "passive"))
      (node (ref "JP86") (pin "1") (pinfunction "1_1") (pintype "passive"))
      (node (ref "JP87") (pin "1") (pinfunction "1_1") (pintype "passive"))
      (node (ref "JP88") (pin "1") (pinfunction "1_1") (pintype "passive"))
      (node (ref "JP89") (pin "1") (pinfunction "1_1") (pintype "passive"))
      (node (ref "JP90") (pin "1") (pinfunction "1_1") (pintype "passive"))
      (node (ref "JP91") (pin "1") (pinfunction "1_1") (pintype "passive"))
      (node (ref "JP92") (pin "1") (pinfunction "1_1") (pintype "passive"))
      (node (ref "JP93") (pin "1") (pinfunction "1_1") (pintype "passive"))
      (node (ref "JP94") (pin "1") (pinfunction "1_1") (pintype "passive"))
      (node (ref "JP95") (pin "1") (pinfunction "1_1") (pintype "passive"))
      (node (ref "JP96") (pin "1") (pinfunction "1_1") (pintype "passive"))
      (node (ref "JP97") (pin "1") (pinfunction "1_1") (pintype "passive"))
      (node (ref "JP98") (pin "1") (pinfunction "1_1") (pintype "passive"))
      (node (ref "JP99") (pin "1") (pinfunction "1_1") (pintype "passive"))
    )
    (net (code "12") (name "Net-(JP113-Pad1)") (class "Default")
      (node (ref "JP113") (pin "1") (pinfunction "1_1") (pintype "passive"))
      (node (ref "JP114") (pin "1") (pinfunction "1_1") (pintype "passive"))
      (node (ref "JP115") (pin "1") (pinfunction "1_1") (pintype "passive"))
      (node (ref "JP117") (pin "1") (pinfunction "1_1") (pintype "passive"))
      (node (ref "JP118") (pin "1") (pinfunction "1_1") (pintype "passive"))
      (node (ref "JP119") (pin "1") (pinfunction "1_1") (pintype "passive"))
      (node (ref "JP120") (pin "1") (pinfunction "1_1") (pintype "passive"))
      (node (ref "JP121") (pin "1") (pinfunction "1_1") (pintype "passive"))
      (node (ref "JP122") (pin "1") (pinfunction "1_1") (pintype "passive"))
      (node (ref "JP123") (pin "1") (pinfunction "1_1") (pintype "passive"))
      (node (ref "JP124") (pin "1") (pinfunction "1_1") (pintype "passive"))
      (node (ref "JP125") (pin "1") (pinfunction "1_1") (pintype "passive"))
      (node (ref "JP126") (pin "1") (pinfunction "1_1") (pintype "passive"))
      (node (ref "JP127") (pin "1") (pinfunction "1_1") (pintype "passive"))
      (node (ref "JP128") (pin "1") (pinfunction "1_1") (pintype "passive"))
      (node (ref "JP129") (pin "1") (pinfunction "1_1") (pintype "passive"))
      (node (ref "JP130") (pin "1") (pinfunction "1_1") (pintype "passive"))
    )
    (net (code "13") (name "Net-(JP116-Pad1)") (class "Default")
      (node (ref "JP116") (pin "1") (pinfunction "1_1") (pintype "passive"))
      (node (ref "JP160") (pin "1") (pinfunction "1_1") (pintype "passive"))
      (node (ref "JP161") (pin "1") (pinfunction "1_1") (pintype "passive"))
      (node (ref "JP162") (pin "1") (pinfunction "1_1") (pintype "passive"))
      (node (ref "JP163") (pin "1") (pinfunction "1_1") (pintype "passive"))
      (node (ref "JP164") (pin "1") (pinfunction "1_1") (pintype "passive"))
      (node (ref "JP165") (pin "1") (pinfunction "1_1") (pintype "passive"))
      (node (ref "JP166") (pin "1") (pinfunction "1_1") (pintype "passive"))
    )
    (net (code "14") (name "Net-(JP131-Pad1)") (class "Default")
      (node (ref "JP131") (pin "1") (pinfunction "1_1") (pintype "passive"))
      (node (ref "JP132") (pin "1") (pinfunction "1_1") (pintype "passive"))
      (node (ref "JP133") (pin "1") (pinfunction "1_1") (pintype "passive"))
      (node (ref "JP134") (pin "1") (pinfunction "1_1") (pintype "passive"))
      (node (ref "JP135") (pin "1") (pinfunction "1_1") (pintype "passive"))
      (node (ref "JP137") (pin "1") (pinfunction "1_1") (pintype "passive"))
      (node (ref "JP138") (pin "1") (pinfunction "1_1") (pintype "passive"))
      (node (ref "JP139") (pin "1") (pinfunction "1_1") (pintype "passive"))
      (node (ref "JP140") (pin "1") (pinfunction "1_1") (pintype "passive"))
    )
    (net (code "15") (name "Net-(JP141-Pad1)") (class "Default")
      (node (ref "JP141") (pin "1") (pinfunction "1_1") (pintype "passive"))
      (node (ref "JP143") (pin "1") (pinfunction "1_1") (pintype "passive"))
      (node (ref "JP144") (pin "1") (pinfunction "1_1") (pintype "passive"))
      (node (ref "JP145") (pin "1") (pinfunction "1_1") (pintype "passive"))
      (node (ref "JP146") (pin "1") (pinfunction "1_1") (pintype "passive"))
      (node (ref "JP147") (pin "1") (pinfunction "1_1") (pintype "passive"))
      (node (ref "JP148") (pin "1") (pinfunction "1_1") (pintype "passive"))
      (node (ref "JP149") (pin "1") (pinfunction "1_1") (pintype "passive"))
      (node (ref "JP150") (pin "1") (pinfunction "1_1") (pintype "passive"))
    )
    (net (code "16") (name "Net-(JP151-Pad1)") (class "Default")
      (node (ref "JP151") (pin "1") (pinfunction "1_1") (pintype "passive"))
      (node (ref "JP152") (pin "1") (pinfunction "1_1") (pintype "passive"))
      (node (ref "JP153") (pin "1") (pinfunction "1_1") (pintype "passive"))
      (node (ref "JP155") (pin "1") (pinfunction "1_1") (pintype "passive"))
      (node (ref "JP156") (pin "1") (pinfunction "1_1") (pintype "passive"))
      (node (ref "JP157") (pin "1") (pinfunction "1_1") (pintype "passive"))
      (node (ref "JP158") (pin "1") (pinfunction "1_1") (pintype "passive"))
      (node (ref "JP74") (pin "1") (pinfunction "1_1") (pintype "passive"))
    )
    (net (code "17") (name "Net-(JP168-Pad1)") (class "Default")
      (node (ref "JP168") (pin "1") (pinfunction "1_1") (pintype "passive"))
      (node (ref "JP170") (pin "1") (pinfunction "1_1") (pintype "passive"))
      (node (ref "JP171") (pin "1") (pinfunction "1_1") (pintype "passive"))
      (node (ref "JP172") (pin "1") (pinfunction "1_1") (pintype "passive"))
      (node (ref "JP173") (pin "1") (pinfunction "1_1") (pintype "passive"))
      (node (ref "JP174") (pin "1") (pinfunction "1_1") (pintype "passive"))
      (node (ref "JP175") (pin "1") (pinfunction "1_1") (pintype "passive"))
      (node (ref "JP176") (pin "1") (pinfunction "1_1") (pintype "passive"))
    )
    (net (code "18") (name "Net-(JP178-Pad1)") (class "Default")
      (node (ref "JP178") (pin "1") (pinfunction "1_1") (pintype "passive"))
      (node (ref "JP179") (pin "1") (pinfunction "1_1") (pintype "passive"))
      (node (ref "JP180") (pin "1") (pinfunction "1_1") (pintype "passive"))
      (node (ref "JP181") (pin "1") (pinfunction "1_1") (pintype "passive"))
      (node (ref "JP182") (pin "1") (pinfunction "1_1") (pintype "passive"))
      (node (ref "JP183") (pin "1") (pinfunction "1_1") (pintype "passive"))
      (node (ref "JP184") (pin "1") (pinfunction "1_1") (pintype "passive"))
      (node (ref "JP185") (pin "1") (pinfunction "1_1") (pintype "passive"))
    )
    (net (code "19") (name "Net-(JP231-Pad1)") (class "Default")
      (node (ref "JP231") (pin "1") (pinfunction "1_1") (pintype "passive"))
      (node (ref "JP232") (pin "1") (pinfunction "1_1") (pintype "passive"))
      (node (ref "JP233") (pin "1") (pinfunction "1_1") (pintype "passive"))
      (node (ref "JP234") (pin "1") (pinfunction "1_1") (pintype "passive"))
      (node (ref "JP235") (pin "1") (pinfunction "1_1") (pintype "passive"))
      (node (ref "JP236") (pin "1") (pinfunction "1_1") (pintype "passive"))
      (node (ref "JP237") (pin "1") (pinfunction "1_1") (pintype "passive"))
      (node (ref "JP239") (pin "1") (pinfunction "1_1") (pintype "passive"))
      (node (ref "JP240") (pin "1") (pinfunction "1_1") (pintype "passive"))
      (node (ref "JP241") (pin "1") (pinfunction "1_1") (pintype "passive"))
      (node (ref "JP242") (pin "1") (pinfunction "1_1") (pintype "passive"))
      (node (ref "JP243") (pin "1") (pinfunction "1_1") (pintype "passive"))
      (node (ref "JP244") (pin "1") (pinfunction "1_1") (pintype "passive"))
      (node (ref "JP245") (pin "1") (pinfunction "1_1") (pintype "passive"))
      (node (ref "JP246") (pin "1") (pinfunction "1_1") (pintype "passive"))
      (node (ref "JP247") (pin "1") (pinfunction "1_1") (pintype "passive"))
      (node (ref "JP248") (pin "1") (pinfunction "1_1") (pintype "passive"))
    )
    (net (code "20") (name "Net-(U$1C-FIL-MID)") (class "Default")
      (node (ref "JP136") (pin "1") (pinfunction "1_1") (pintype "passive"))
      (node (ref "JP73") (pin "1") (pinfunction "1_1") (pintype "passive"))
      (node (ref "U$1") (pin "9") (pinfunction "FIL-MID_9") (pintype "bidirectional"))
    )
    (net (code "21") (name "Net-(U$1C-FIL1)") (class "Default")
      (node (ref "JP142") (pin "1") (pinfunction "1_1") (pintype "passive"))
      (node (ref "JP77") (pin "1") (pinfunction "1_1") (pintype "passive"))
      (node (ref "U$1") (pin "4") (pinfunction "FIL1_4") (pintype "bidirectional"))
      (node (ref "U$1") (pin "5") (pinfunction "FIL2_5") (pintype "bidirectional"))
    )
  )
)
